# sensor_eeprom_v2_0.net
KiCad netlist of a schematic drawn in EAGLE
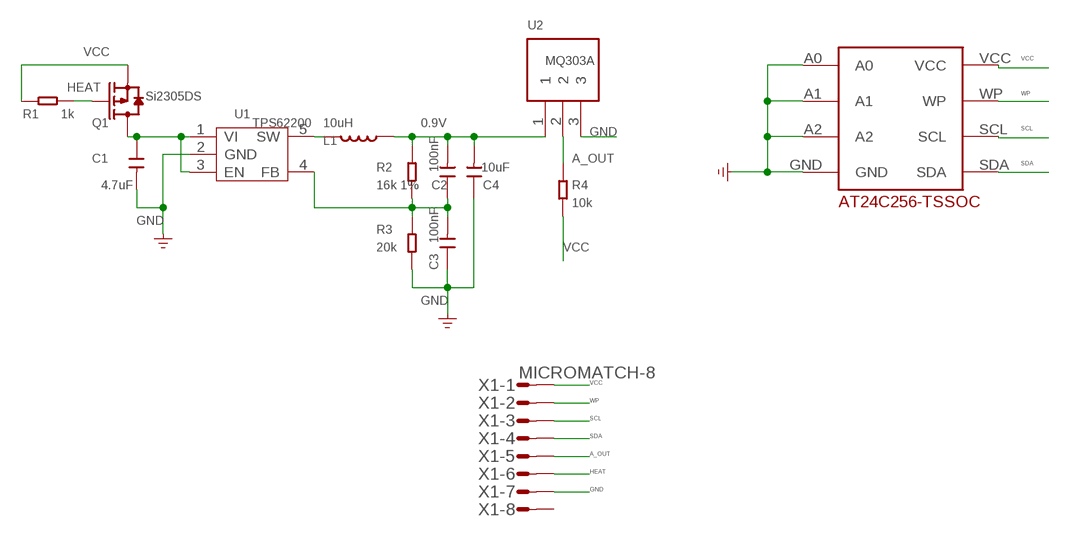
[diagram p0: schematic, sheet 1]

(export (version "E")
  (design (tool "Eeschema 10.0.6"))
  (components
    (comp (ref "C1")
      (value "4.7uF")
      (footprint "eagle-import:C0805")
      (libsource (lib "eagle-import") (part "C-0805"))
    )
    (comp (ref "C2")
      (value "100nF")
      (footprint "eagle-import:C0603")
      (libsource (lib "eagle-import") (part "C-0603"))
    )
    (comp (ref "C3")
      (value "100nF")
      (footprint "eagle-import:C0603")
      (libsource (lib "eagle-import") (part "C-0603"))
    )
    (comp (ref "C4")
      (value "10uF")
      (footprint "eagle-import:C0805")
      (libsource (lib "eagle-import") (part "C-0805"))
    )
    (comp (ref "L1")
      (value "10uH")
      (footprint "eagle-import:PIO73")
      (libsource (lib "eagle-import") (part "L'PIO73'"))
    )
    (comp (ref "Q1")
      (value "Si2305DS")
      (footprint "eagle-import:SOT23")
      (libsource (lib "eagle-import") (part "MOSFET-P'SI2323CDS/SI2305DS{lt}BR{gt}'"))
    )
    (comp (ref "R1")
      (value "1k")
      (footprint "eagle-import:R0603")
      (libsource (lib "eagle-import") (part "R-0603"))
    )
    (comp (ref "R2")
      (value "16k 1%")
      (footprint "eagle-import:R0603")
      (libsource (lib "eagle-import") (part "R-0603"))
    )
    (comp (ref "R3")
      (value "20k")
      (footprint "eagle-import:R0603")
      (libsource (lib "eagle-import") (part "R-0603"))
    )
    (comp (ref "R4")
      (value "10k")
      (footprint "eagle-import:R0603")
      (libsource (lib "eagle-import") (part "R-0603"))
    )
    (comp (ref "U$1")
      (value "DECADE-AT24C256-10TI-2.7")
      (footprint "eagle-import:DECADE-AT24CXX")
      (libsource (lib "eagle-import") (part "DECADE-AT24C256-10TI-2.7"))
    )
    (comp (ref "U1")
      (value "TPS62200")
      (footprint "eagle-import:SOT23-5")
      (libsource (lib "eagle-import") (part "TPS62200DBV"))
    )
    (comp (ref "U2")
      (value "MQ303A")
      (footprint "eagle-import:MQ303A")
      (libsource (lib "eagle-import") (part "MQ303A"))
    )
    (comp (ref "X1")
      (value "MICROMATCH-8")
      (footprint "eagle-import:MICROMATCH-8")
      (fields (field (name "MF") "FARNELL") (field (name "MPN") "7-215464-8"))
      (libsource (lib "eagle-import") (part "MICROMATCH-8"))
    )
  )
  (nets
    (net (code "1") (name "/0.9V") (class "Default")
      (node (ref "C2") (pin "2") (pinfunction "2_2") (pintype "passive"))
      (node (ref "C4") (pin "2") (pinfunction "2_2") (pintype "passive"))
      (node (ref "L1") (pin "2") (pinfunction "2_2") (pintype "passive"))
      (node (ref "R2") (pin "1") (pinfunction "1_1") (pintype "passive"))
      (node (ref "U2") (pin "1") (pinfunction "1_1") (pintype "bidirectional"))
    )
    (net (code "2") (name "/A_OUT") (class "Default")
      (node (ref "R4") (pin "1") (pinfunction "1_1") (pintype "passive"))
      (node (ref "U2") (pin "2") (pinfunction "2_2") (pintype "bidirectional"))
      (node (ref "X1") (pin "5") (pinfunction "S_5") (pintype "passive"))
    )
    (net (code "3") (name "/HEAT") (class "Default")
      (node (ref "Q1") (pin "1") (pinfunction "G_1") (pintype "passive"))
      (node (ref "R1") (pin "1") (pinfunction "1_1") (pintype "passive"))
      (node (ref "X1") (pin "6") (pinfunction "S_6") (pintype "passive"))
    )
    (net (code "4") (name "/SCL") (class "Default")
      (node (ref "U$1") (pin "SCL") (pinfunction "SCL_SCL") (pintype "bidirectional"))
      (node (ref "X1") (pin "3") (pinfunction "S_3") (pintype "passive"))
    )
    (net (code "5") (name "/SDA") (class "Default")
      (node (ref "U$1") (pin "SDA") (pinfunction "SDA_SDA") (pintype "bidirectional"))
      (node (ref "X1") (pin "4") (pinfunction "S_4") (pintype "passive"))
    )
    (net (code "6") (name "/VCC") (class "Default")
      (node (ref "Q1") (pin "2") (pinfunction "S_2") (pintype "passive"))
      (node (ref "R1") (pin "2") (pinfunction "2_2") (pintype "passive"))
      (node (ref "R4") (pin "2") (pinfunction "2_2") (pintype "passive"))
      (node (ref "U$1") (pin "VCC") (pinfunction "VCC_VCC") (pintype "bidirectional"))
      (node (ref "X1") (pin "1") (pinfunction "S_1") (pintype "passive"))
    )
    (net (code "7") (name "/WP") (class "Default")
      (node (ref "U$1") (pin "WP") (pinfunction "WP_WP") (pintype "bidirectional"))
      (node (ref "X1") (pin "2") (pinfunction "S_2") (pintype "passive"))
    )
    (net (code "8") (name "GND_POWER") (class "Default")
      (node (ref "C1") (pin "2") (pinfunction "2_2") (pintype "passive"))
      (node (ref "C3") (pin "1") (pinfunction "1_1") (pintype "passive"))
      (node (ref "C4") (pin "1") (pinfunction "1_1") (pintype "passive"))
      (node (ref "R3") (pin "2") (pinfunction "2_2") (pintype "passive"))
      (node (ref "U$1") (pin "A0") (pinfunction "A0_A0") (pintype "bidirectional"))
      (node (ref "U$1") (pin "A1") (pinfunction "A1_A1") (pintype "bidirectional"))
      (node (ref "U$1") (pin "A2") (pinfunction "A2_A2") (pintype "bidirectional"))
      (node (ref "U$1") (pin "GND") (pinfunction "GND_GND") (pintype "bidirectional"))
      (node (ref "U1") (pin "2") (pinfunction "GND_2") (pintype "power_in"))
      (node (ref "U2") (pin "3") (pinfunction "3_3") (pintype "bidirectional"))
      (node (ref "X1") (pin "7") (pinfunction "S_7") (pintype "passive"))
    )
    (net (code "9") (name "Net-(Q1-D)") (class "Default")
      (node (ref "C1") (pin "1") (pinfunction "1_1") (pintype "passive"))
      (node (ref "Q1") (pin "3") (pinfunction "D_3") (pintype "passive"))
      (node (ref "U1") (pin "1") (pinfunction "VI_1") (pintype "input"))
      (node (ref "U1") (pin "3") (pinfunction "EN_3") (pintype "input"))
    )
    (net (code "10") (name "Net-(U1-FB)") (class "Default")
      (node (ref "C2") (pin "1") (pinfunction "1_1") (pintype "passive"))
      (node (ref "C3") (pin "2") (pinfunction "2_2") (pintype "passive"))
      (node (ref "R2") (pin "2") (pinfunction "2_2") (pintype "passive"))
      (node (ref "R3") (pin "1") (pinfunction "1_1") (pintype "passive"))
      (node (ref "U1") (pin "4") (pinfunction "FB_4") (pintype "input"))
    )
    (net (code "11") (name "Net-(U1-SW)") (class "Default")
      (node (ref "L1") (pin "1") (pinfunction "1_1") (pintype "passive"))
      (node (ref "U1") (pin "5") (pinfunction "SW_5") (pintype "bidirectional"))
    )
    (net (code "12") (name "unconnected-(X1H-S-Pad8)") (class "Default")
      (node (ref "X1") (pin "8") (pinfunction "S_8") (pintype "passive"))
    )
  )
)
